# Main.net
KiCad netlist of a schematic drawn in EAGLE
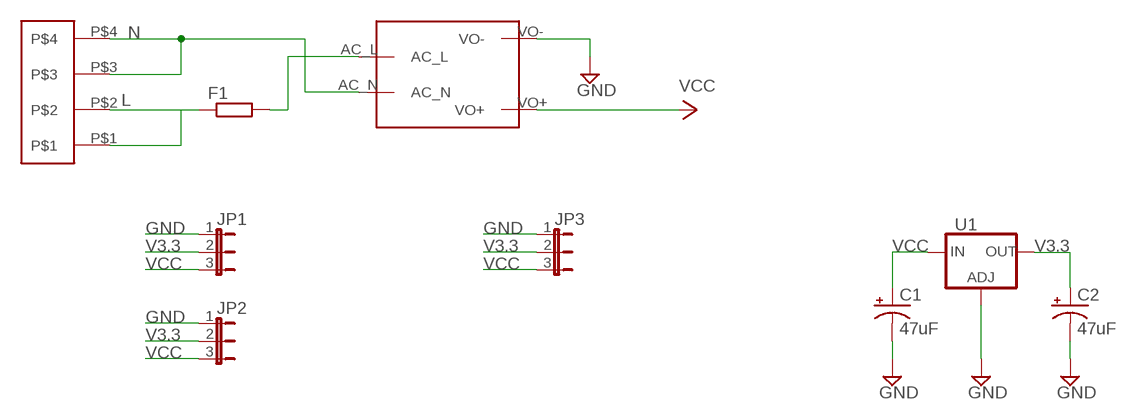
[diagram p0: schematic, sheet 1]

(export (version "E")
  (design (tool "Eeschema 10.0.6"))
  (components
    (comp (ref "17928891")
      (value "1792889")
      (footprint "eagle-import:1792889")
      (libsource (lib "eagle-import") (part "1792889"))
    )
    (comp (ref "C1")
      (value "47uF")
      (footprint "eagle-import:EIA3528")
      (libsource (lib "eagle-import") (part "CAP_POL3528"))
    )
    (comp (ref "C2")
      (value "47uF")
      (footprint "eagle-import:EIA3528")
      (libsource (lib "eagle-import") (part "CAP_POL3528"))
    )
    (comp (ref "F1")
      (value "R-EU_R2010W")
      (footprint "eagle-import:R2010W")
      (libsource (lib "eagle-import") (part "R-EU_R2010W"))
    )
    (comp (ref "JP1")
      (value "JP2E")
      (footprint "eagle-import:JP2")
      (libsource (lib "eagle-import") (part "JP2E"))
    )
    (comp (ref "JP2")
      (value "JP2E")
      (footprint "eagle-import:JP2")
      (libsource (lib "eagle-import") (part "JP2E"))
    )
    (comp (ref "JP3")
      (value "JP2E")
      (footprint "eagle-import:JP2")
      (libsource (lib "eagle-import") (part "JP2E"))
    )
    (comp (ref "PWR1")
      (value "MAINS_CONVERTERS")
      (footprint "eagle-import:HLK-PM01")
      (libsource (lib "eagle-import") (part "MAINS_CONVERTERS"))
    )
    (comp (ref "U1")
      (value "V_REG_3.3V")
      (footprint "eagle-import:SOT223")
      (libsource (lib "eagle-import") (part "V_REG_317SMD"))
    )
  )
  (nets
    (net (code "1") (name "/L") (class "Default")
      (node (ref "17928891") (pin "P$1") (pinfunction "P$1_P$1") (pintype "power_in"))
      (node (ref "17928891") (pin "P$2") (pinfunction "P$2_P$2") (pintype "power_in"))
      (node (ref "F1") (pin "1") (pinfunction "1_1") (pintype "passive"))
    )
    (net (code "2") (name "/N") (class "Default")
      (node (ref "17928891") (pin "P$3") (pinfunction "P$3_P$3") (pintype "power_in"))
      (node (ref "17928891") (pin "P$4") (pinfunction "P$4_P$4") (pintype "power_in"))
      (node (ref "PWR1") (pin "AC_N") (pinfunction "AC_N_AC_N") (pintype "input"))
    )
    (net (code "3") (name "/V3.3") (class "Default")
      (node (ref "C2") (pin "A") (pinfunction "+_A") (pintype "passive"))
      (node (ref "JP1") (pin "2") (pinfunction "2_2") (pintype "passive"))
      (node (ref "JP2") (pin "2") (pinfunction "2_2") (pintype "passive"))
      (node (ref "JP3") (pin "2") (pinfunction "2_2") (pintype "passive"))
      (node (ref "U1") (pin "2") (pinfunction "OUT_2") (pintype "output"))
    )
    (net (code "4") (name "GND") (class "Default")
      (node (ref "C1") (pin "C") (pinfunction "-_C") (pintype "passive"))
      (node (ref "C2") (pin "C") (pinfunction "-_C") (pintype "passive"))
      (node (ref "JP1") (pin "1") (pinfunction "1_1") (pintype "passive"))
      (node (ref "JP2") (pin "1") (pinfunction "1_1") (pintype "passive"))
      (node (ref "JP3") (pin "1") (pinfunction "1_1") (pintype "passive"))
      (node (ref "PWR1") (pin "VO-") (pinfunction "VO-_VO-") (pintype "output"))
      (node (ref "U1") (pin "1") (pinfunction "ADJ_1") (pintype "input"))
    )
    (net (code "5") (name "Net-(F1-Pad2)") (class "Default")
      (node (ref "F1") (pin "2") (pinfunction "2_2") (pintype "passive"))
      (node (ref "PWR1") (pin "AC_L") (pinfunction "AC_L_AC_L") (pintype "input"))
    )
    (net (code "6") (name "VCC") (class "Default")
      (node (ref "C1") (pin "A") (pinfunction "+_A") (pintype "passive"))
      (node (ref "JP1") (pin "3") (pinfunction "3_3") (pintype "passive"))
      (node (ref "JP2") (pin "3") (pinfunction "3_3") (pintype "passive"))
      (node (ref "JP3") (pin "3") (pinfunction "3_3") (pintype "passive"))
      (node (ref "PWR1") (pin "VO+") (pinfunction "VO+_VO+") (pintype "output"))
      (node (ref "U1") (pin "3") (pinfunction "IN_3") (pintype "input"))
    )
  )
)
